# FPGA.net
KiCad netlist of a schematic drawn in Altium Designer
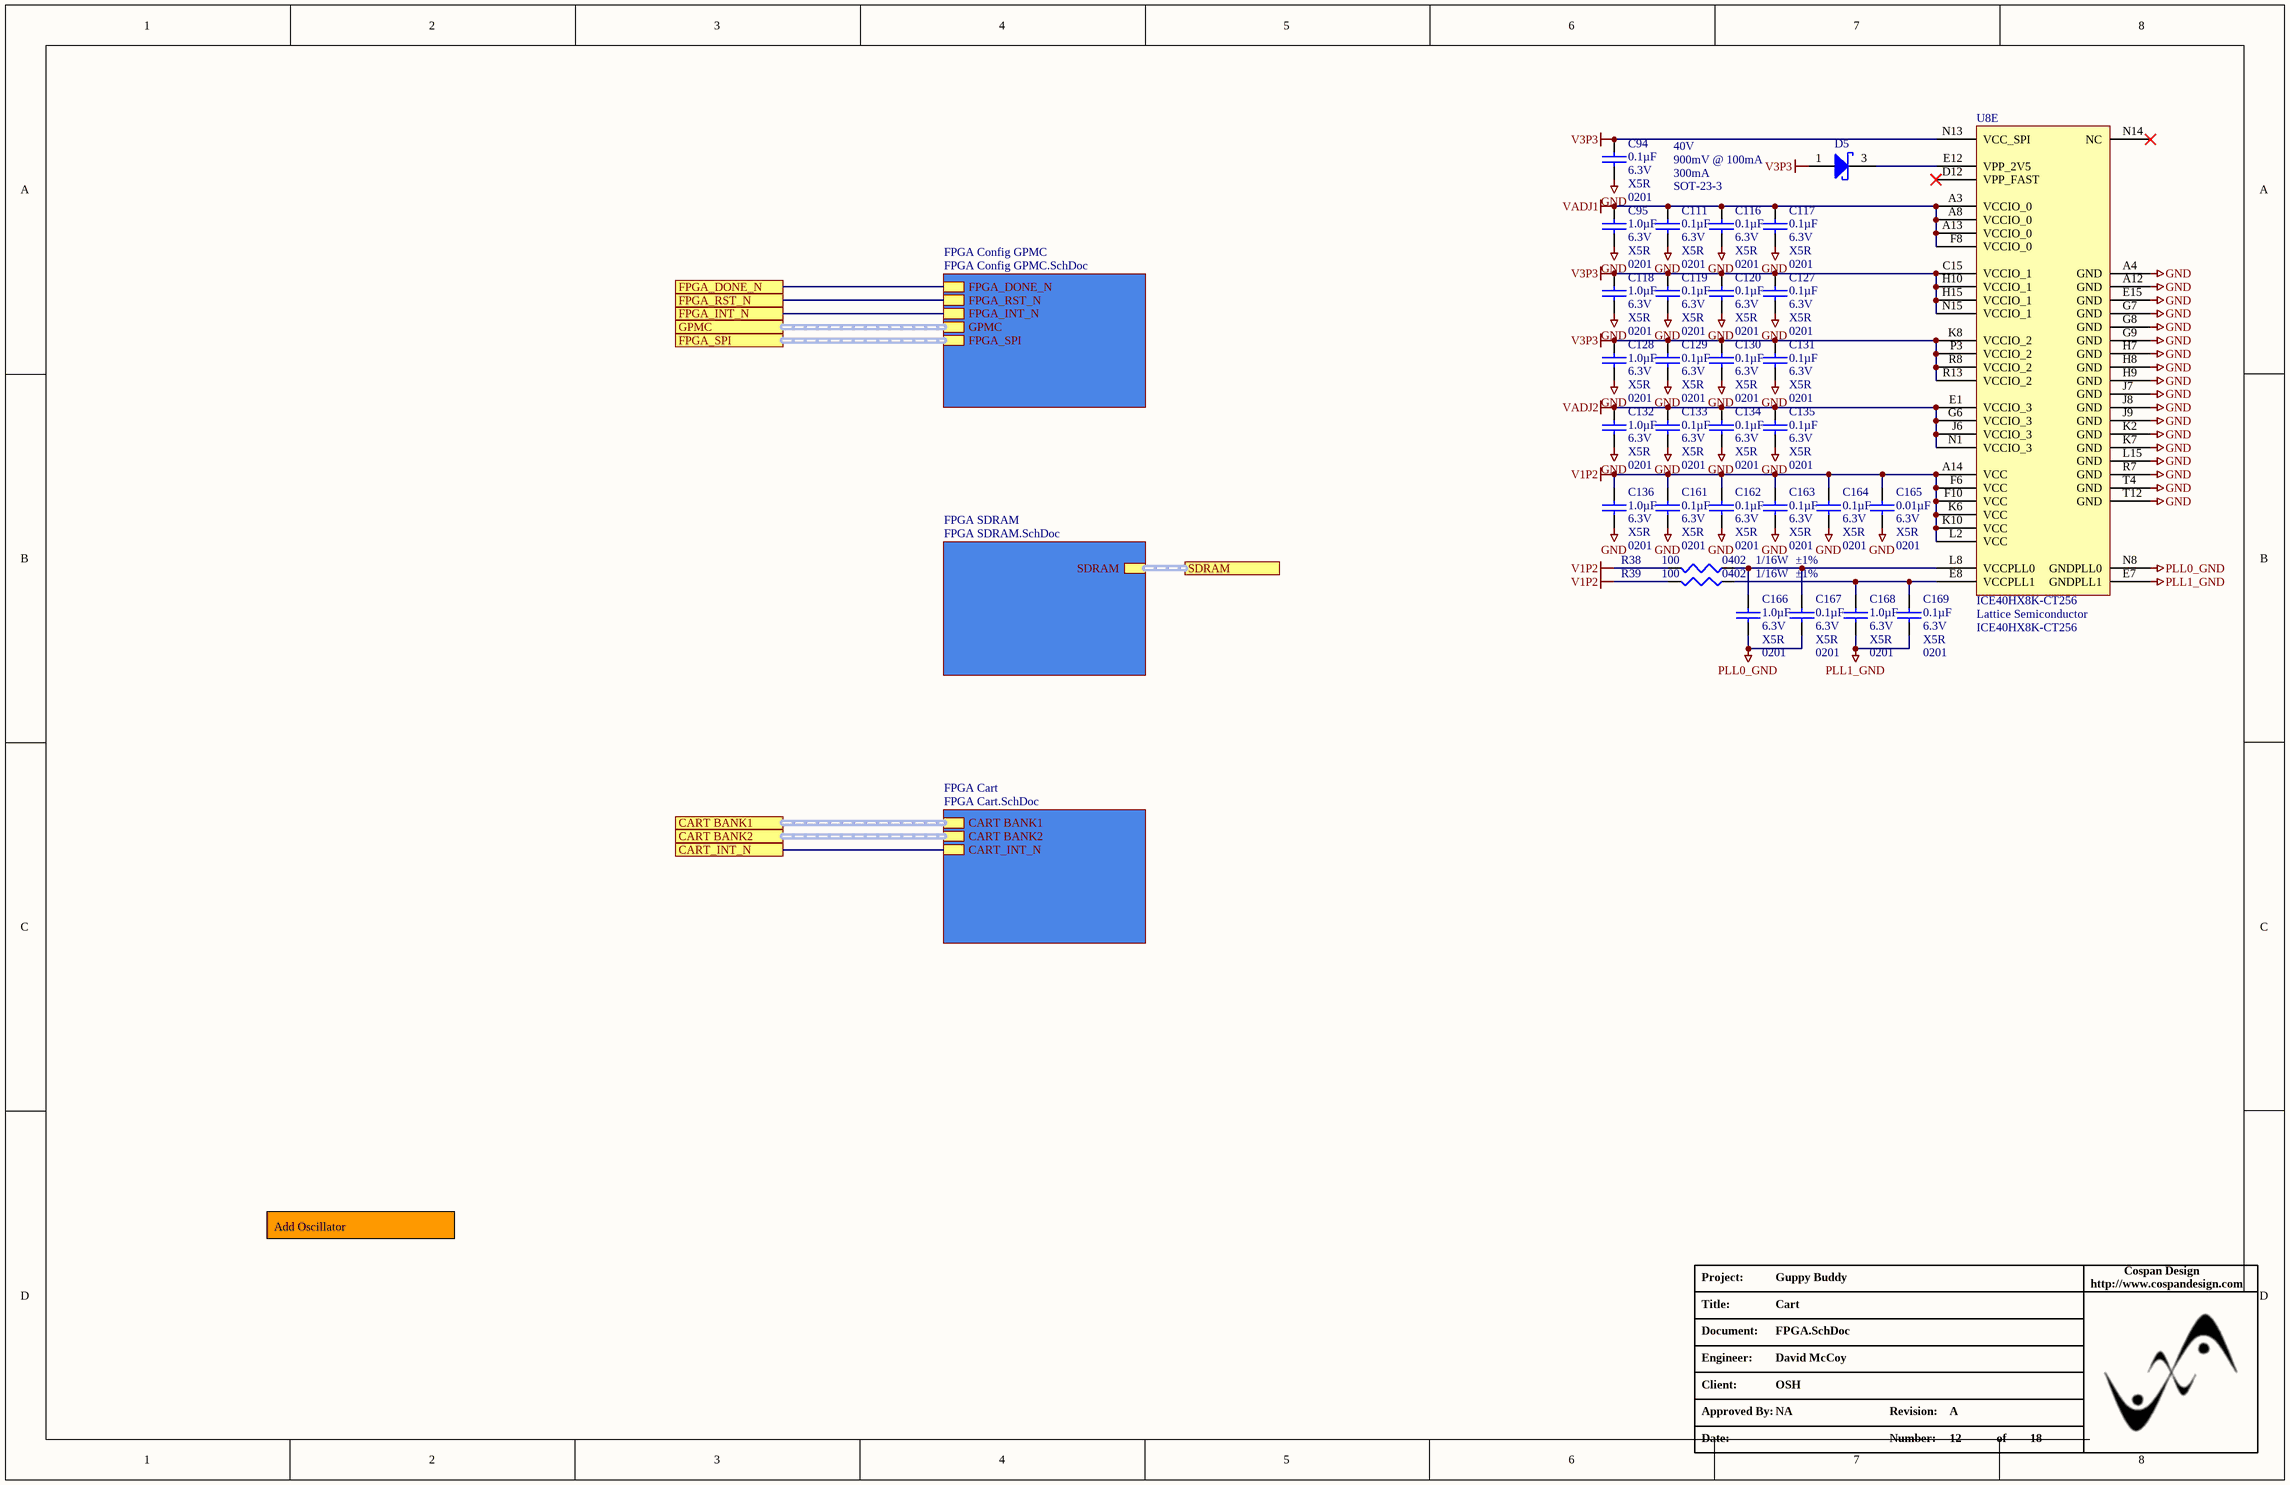
[diagram p0: FPGA.SchDoc]

(export (version "E")
  (design (tool "Eeschema 10.0.6"))
  (components
    (comp (ref "C94")
      (value "0.1UF")
      (footprint "CAPC0201")
      (description "CAP CER 0.1UF 6.3V 10% X5R 0201")
      (fields
        (field (name "MANUFACTURER") "Murata Electronics North America")
        (field (name "MANUFACTURER PART NUMBER") "GRM033R60J104KE19D")
        (field (name "CAPACITANCE") "0.1µF")
        (field (name "VOLTAGE - RATED") "6.3V")
        (field (name "TEMPERATURE COEFFICIENT") "X5R")
        (field (name "PACKAGE / CASE") "0201")
      )
      (libsource (lib "Main Library") (part "C_0201_0.1UF"))
    )
    (comp (ref "C95")
      (value "1.0UF")
      (footprint "CAPC0201")
      (description "CAP CER 1UF 6.3V 20% X5R 0201")
      (fields
        (field (name "MANUFACTURER") "AVX")
        (field (name "MANUFACTURER PART NUMBER") "02016D105KAT2A")
        (field (name "CAPACITANCE") "1.0µF")
        (field (name "VOLTAGE - RATED") "6.3V")
        (field (name "TEMPERATURE COEFFICIENT") "X5R")
        (field (name "PACKAGE / CASE") "0201")
      )
      (libsource (lib "Main Library") (part "C_0201_1.0UF"))
    )
    (comp (ref "C111")
      (value "0.1UF")
      (footprint "CAPC0201")
      (description "CAP CER 0.1UF 6.3V 10% X5R 0201")
      (fields
        (field (name "MANUFACTURER") "Murata Electronics North America")
        (field (name "MANUFACTURER PART NUMBER") "GRM033R60J104KE19D")
        (field (name "CAPACITANCE") "0.1µF")
        (field (name "VOLTAGE - RATED") "6.3V")
        (field (name "TEMPERATURE COEFFICIENT") "X5R")
        (field (name "PACKAGE / CASE") "0201")
      )
      (libsource (lib "Main Library") (part "C_0201_0.1UF"))
    )
    (comp (ref "C116")
      (value "0.1UF")
      (footprint "CAPC0201")
      (description "CAP CER 0.1UF 6.3V 10% X5R 0201")
      (fields
        (field (name "MANUFACTURER") "Murata Electronics North America")
        (field (name "MANUFACTURER PART NUMBER") "GRM033R60J104KE19D")
        (field (name "CAPACITANCE") "0.1µF")
        (field (name "VOLTAGE - RATED") "6.3V")
        (field (name "TEMPERATURE COEFFICIENT") "X5R")
        (field (name "PACKAGE / CASE") "0201")
      )
      (libsource (lib "Main Library") (part "C_0201_0.1UF"))
    )
    (comp (ref "C117")
      (value "0.1UF")
      (footprint "CAPC0201")
      (description "CAP CER 0.1UF 6.3V 10% X5R 0201")
      (fields
        (field (name "MANUFACTURER") "Murata Electronics North America")
        (field (name "MANUFACTURER PART NUMBER") "GRM033R60J104KE19D")
        (field (name "CAPACITANCE") "0.1µF")
        (field (name "VOLTAGE - RATED") "6.3V")
        (field (name "TEMPERATURE COEFFICIENT") "X5R")
        (field (name "PACKAGE / CASE") "0201")
      )
      (libsource (lib "Main Library") (part "C_0201_0.1UF"))
    )
    (comp (ref "C118")
      (value "1.0UF")
      (footprint "CAPC0201")
      (description "CAP CER 1UF 6.3V 20% X5R 0201")
      (fields
        (field (name "MANUFACTURER") "AVX")
        (field (name "MANUFACTURER PART NUMBER") "02016D105KAT2A")
        (field (name "CAPACITANCE") "1.0µF")
        (field (name "VOLTAGE - RATED") "6.3V")
        (field (name "TEMPERATURE COEFFICIENT") "X5R")
        (field (name "PACKAGE / CASE") "0201")
      )
      (libsource (lib "Main Library") (part "C_0201_1.0UF"))
    )
    (comp (ref "C119")
      (value "0.1UF")
      (footprint "CAPC0201")
      (description "CAP CER 0.1UF 6.3V 10% X5R 0201")
      (fields
        (field (name "MANUFACTURER") "Murata Electronics North America")
        (field (name "MANUFACTURER PART NUMBER") "GRM033R60J104KE19D")
        (field (name "CAPACITANCE") "0.1µF")
        (field (name "VOLTAGE - RATED") "6.3V")
        (field (name "TEMPERATURE COEFFICIENT") "X5R")
        (field (name "PACKAGE / CASE") "0201")
      )
      (libsource (lib "Main Library") (part "C_0201_0.1UF"))
    )
    (comp (ref "C120")
      (value "0.1UF")
      (footprint "CAPC0201")
      (description "CAP CER 0.1UF 6.3V 10% X5R 0201")
      (fields
        (field (name "MANUFACTURER") "Murata Electronics North America")
        (field (name "MANUFACTURER PART NUMBER") "GRM033R60J104KE19D")
        (field (name "CAPACITANCE") "0.1µF")
        (field (name "VOLTAGE - RATED") "6.3V")
        (field (name "TEMPERATURE COEFFICIENT") "X5R")
        (field (name "PACKAGE / CASE") "0201")
      )
      (libsource (lib "Main Library") (part "C_0201_0.1UF"))
    )
    (comp (ref "C127")
      (value "0.1UF")
      (footprint "CAPC0201")
      (description "CAP CER 0.1UF 6.3V 10% X5R 0201")
      (fields
        (field (name "MANUFACTURER") "Murata Electronics North America")
        (field (name "MANUFACTURER PART NUMBER") "GRM033R60J104KE19D")
        (field (name "CAPACITANCE") "0.1µF")
        (field (name "VOLTAGE - RATED") "6.3V")
        (field (name "TEMPERATURE COEFFICIENT") "X5R")
        (field (name "PACKAGE / CASE") "0201")
      )
      (libsource (lib "Main Library") (part "C_0201_0.1UF"))
    )
    (comp (ref "C128")
      (value "1.0UF")
      (footprint "CAPC0201")
      (description "CAP CER 1UF 6.3V 20% X5R 0201")
      (fields
        (field (name "MANUFACTURER") "AVX")
        (field (name "MANUFACTURER PART NUMBER") "02016D105KAT2A")
        (field (name "CAPACITANCE") "1.0µF")
        (field (name "VOLTAGE - RATED") "6.3V")
        (field (name "TEMPERATURE COEFFICIENT") "X5R")
        (field (name "PACKAGE / CASE") "0201")
      )
      (libsource (lib "Main Library") (part "C_0201_1.0UF"))
    )
    (comp (ref "C129")
      (value "0.1UF")
      (footprint "CAPC0201")
      (description "CAP CER 0.1UF 6.3V 10% X5R 0201")
      (fields
        (field (name "MANUFACTURER") "Murata Electronics North America")
        (field (name "MANUFACTURER PART NUMBER") "GRM033R60J104KE19D")
        (field (name "CAPACITANCE") "0.1µF")
        (field (name "VOLTAGE - RATED") "6.3V")
        (field (name "TEMPERATURE COEFFICIENT") "X5R")
        (field (name "PACKAGE / CASE") "0201")
      )
      (libsource (lib "Main Library") (part "C_0201_0.1UF"))
    )
    (comp (ref "C130")
      (value "0.1UF")
      (footprint "CAPC0201")
      (description "CAP CER 0.1UF 6.3V 10% X5R 0201")
      (fields
        (field (name "MANUFACTURER") "Murata Electronics North America")
        (field (name "MANUFACTURER PART NUMBER") "GRM033R60J104KE19D")
        (field (name "CAPACITANCE") "0.1µF")
        (field (name "VOLTAGE - RATED") "6.3V")
        (field (name "TEMPERATURE COEFFICIENT") "X5R")
        (field (name "PACKAGE / CASE") "0201")
      )
      (libsource (lib "Main Library") (part "C_0201_0.1UF"))
    )
    (comp (ref "C131")
      (value "0.1UF")
      (footprint "CAPC0201")
      (description "CAP CER 0.1UF 6.3V 10% X5R 0201")
      (fields
        (field (name "MANUFACTURER") "Murata Electronics North America")
        (field (name "MANUFACTURER PART NUMBER") "GRM033R60J104KE19D")
        (field (name "CAPACITANCE") "0.1µF")
        (field (name "VOLTAGE - RATED") "6.3V")
        (field (name "TEMPERATURE COEFFICIENT") "X5R")
        (field (name "PACKAGE / CASE") "0201")
      )
      (libsource (lib "Main Library") (part "C_0201_0.1UF"))
    )
    (comp (ref "C132")
      (value "1.0UF")
      (footprint "CAPC0201")
      (description "CAP CER 1UF 6.3V 20% X5R 0201")
      (fields
        (field (name "MANUFACTURER") "AVX")
        (field (name "MANUFACTURER PART NUMBER") "02016D105KAT2A")
        (field (name "CAPACITANCE") "1.0µF")
        (field (name "VOLTAGE - RATED") "6.3V")
        (field (name "TEMPERATURE COEFFICIENT") "X5R")
        (field (name "PACKAGE / CASE") "0201")
      )
      (libsource (lib "Main Library") (part "C_0201_1.0UF"))
    )
    (comp (ref "C133")
      (value "0.1UF")
      (footprint "CAPC0201")
      (description "CAP CER 0.1UF 6.3V 10% X5R 0201")
      (fields
        (field (name "MANUFACTURER") "Murata Electronics North America")
        (field (name "MANUFACTURER PART NUMBER") "GRM033R60J104KE19D")
        (field (name "CAPACITANCE") "0.1µF")
        (field (name "VOLTAGE - RATED") "6.3V")
        (field (name "TEMPERATURE COEFFICIENT") "X5R")
        (field (name "PACKAGE / CASE") "0201")
      )
      (libsource (lib "Main Library") (part "C_0201_0.1UF"))
    )
    (comp (ref "C134")
      (value "0.1UF")
      (footprint "CAPC0201")
      (description "CAP CER 0.1UF 6.3V 10% X5R 0201")
      (fields
        (field (name "MANUFACTURER") "Murata Electronics North America")
        (field (name "MANUFACTURER PART NUMBER") "GRM033R60J104KE19D")
        (field (name "CAPACITANCE") "0.1µF")
        (field (name "VOLTAGE - RATED") "6.3V")
        (field (name "TEMPERATURE COEFFICIENT") "X5R")
        (field (name "PACKAGE / CASE") "0201")
      )
      (libsource (lib "Main Library") (part "C_0201_0.1UF"))
    )
    (comp (ref "C135")
      (value "0.1UF")
      (footprint "CAPC0201")
      (description "CAP CER 0.1UF 6.3V 10% X5R 0201")
      (fields
        (field (name "MANUFACTURER") "Murata Electronics North America")
        (field (name "MANUFACTURER PART NUMBER") "GRM033R60J104KE19D")
        (field (name "CAPACITANCE") "0.1µF")
        (field (name "VOLTAGE - RATED") "6.3V")
        (field (name "TEMPERATURE COEFFICIENT") "X5R")
        (field (name "PACKAGE / CASE") "0201")
      )
      (libsource (lib "Main Library") (part "C_0201_0.1UF"))
    )
    (comp (ref "C136")
      (value "1.0UF")
      (footprint "CAPC0201")
      (description "CAP CER 1UF 6.3V 20% X5R 0201")
      (fields
        (field (name "MANUFACTURER") "AVX")
        (field (name "MANUFACTURER PART NUMBER") "02016D105KAT2A")
        (field (name "CAPACITANCE") "1.0µF")
        (field (name "VOLTAGE - RATED") "6.3V")
        (field (name "TEMPERATURE COEFFICIENT") "X5R")
        (field (name "PACKAGE / CASE") "0201")
      )
      (libsource (lib "Main Library") (part "C_0201_1.0UF"))
    )
    (comp (ref "C161")
      (value "0.1UF")
      (footprint "CAPC0201")
      (description "CAP CER 0.1UF 6.3V 10% X5R 0201")
      (fields
        (field (name "MANUFACTURER") "Murata Electronics North America")
        (field (name "MANUFACTURER PART NUMBER") "GRM033R60J104KE19D")
        (field (name "CAPACITANCE") "0.1µF")
        (field (name "VOLTAGE - RATED") "6.3V")
        (field (name "TEMPERATURE COEFFICIENT") "X5R")
        (field (name "PACKAGE / CASE") "0201")
      )
      (libsource (lib "Main Library") (part "C_0201_0.1UF"))
    )
    (comp (ref "C162")
      (value "0.1UF")
      (footprint "CAPC0201")
      (description "CAP CER 0.1UF 6.3V 10% X5R 0201")
      (fields
        (field (name "MANUFACTURER") "Murata Electronics North America")
        (field (name "MANUFACTURER PART NUMBER") "GRM033R60J104KE19D")
        (field (name "CAPACITANCE") "0.1µF")
        (field (name "VOLTAGE - RATED") "6.3V")
        (field (name "TEMPERATURE COEFFICIENT") "X5R")
        (field (name "PACKAGE / CASE") "0201")
      )
      (libsource (lib "Main Library") (part "C_0201_0.1UF"))
    )
    (comp (ref "C163")
      (value "0.1UF")
      (footprint "CAPC0201")
      (description "CAP CER 0.1UF 6.3V 10% X5R 0201")
      (fields
        (field (name "MANUFACTURER") "Murata Electronics North America")
        (field (name "MANUFACTURER PART NUMBER") "GRM033R60J104KE19D")
        (field (name "CAPACITANCE") "0.1µF")
        (field (name "VOLTAGE - RATED") "6.3V")
        (field (name "TEMPERATURE COEFFICIENT") "X5R")
        (field (name "PACKAGE / CASE") "0201")
      )
      (libsource (lib "Main Library") (part "C_0201_0.1UF"))
    )
    (comp (ref "C164")
      (value "0.1UF")
      (footprint "CAPC0201")
      (description "CAP CER 0.1UF 6.3V 10% X5R 0201")
      (fields
        (field (name "MANUFACTURER") "Murata Electronics North America")
        (field (name "MANUFACTURER PART NUMBER") "GRM033R60J104KE19D")
        (field (name "CAPACITANCE") "0.1µF")
        (field (name "VOLTAGE - RATED") "6.3V")
        (field (name "TEMPERATURE COEFFICIENT") "X5R")
        (field (name "PACKAGE / CASE") "0201")
      )
      (libsource (lib "Main Library") (part "C_0201_0.1UF"))
    )
    (comp (ref "C165")
      (value "0.01UF")
      (footprint "CAPC0201")
      (description "CAP CER 10000PF 6.3V X5R 0201")
      (fields
        (field (name "MANUFACTURER") "TDK Corporation")
        (field (name "MANUFACTURER PART NUMBER") "C0603X5R0J103M")
        (field (name "CAPACITANCE") "0.01µF")
        (field (name "VOLTAGE - RATED") "6.3V")
        (field (name "TEMPERATURE COEFFICIENT") "X5R")
        (field (name "PACKAGE / CASE") "0201")
      )
      (libsource (lib "Main Library") (part "C_0201_0.01UF"))
    )
    (comp (ref "C166")
      (value "1.0UF")
      (footprint "CAPC0201")
      (description "CAP CER 1UF 6.3V 20% X5R 0201")
      (fields
        (field (name "MANUFACTURER") "AVX")
        (field (name "MANUFACTURER PART NUMBER") "02016D105KAT2A")
        (field (name "CAPACITANCE") "1.0µF")
        (field (name "VOLTAGE - RATED") "6.3V")
        (field (name "TEMPERATURE COEFFICIENT") "X5R")
        (field (name "PACKAGE / CASE") "0201")
      )
      (libsource (lib "Main Library") (part "C_0201_1.0UF"))
    )
    (comp (ref "C167")
      (value "0.1UF")
      (footprint "CAPC0201")
      (description "CAP CER 0.1UF 6.3V 10% X5R 0201")
      (fields
        (field (name "MANUFACTURER") "Murata Electronics North America")
        (field (name "MANUFACTURER PART NUMBER") "GRM033R60J104KE19D")
        (field (name "CAPACITANCE") "0.1µF")
        (field (name "VOLTAGE - RATED") "6.3V")
        (field (name "TEMPERATURE COEFFICIENT") "X5R")
        (field (name "PACKAGE / CASE") "0201")
      )
      (libsource (lib "Main Library") (part "C_0201_0.1UF"))
    )
    (comp (ref "C168")
      (value "1.0UF")
      (footprint "CAPC0201")
      (description "CAP CER 1UF 6.3V 20% X5R 0201")
      (fields
        (field (name "MANUFACTURER") "AVX")
        (field (name "MANUFACTURER PART NUMBER") "02016D105KAT2A")
        (field (name "CAPACITANCE") "1.0µF")
        (field (name "VOLTAGE - RATED") "6.3V")
        (field (name "TEMPERATURE COEFFICIENT") "X5R")
        (field (name "PACKAGE / CASE") "0201")
      )
      (libsource (lib "Main Library") (part "C_0201_1.0UF"))
    )
    (comp (ref "C169")
      (value "0.1UF")
      (footprint "CAPC0201")
      (description "CAP CER 0.1UF 6.3V 10% X5R 0201")
      (fields
        (field (name "MANUFACTURER") "Murata Electronics North America")
        (field (name "MANUFACTURER PART NUMBER") "GRM033R60J104KE19D")
        (field (name "CAPACITANCE") "0.1µF")
        (field (name "VOLTAGE - RATED") "6.3V")
        (field (name "TEMPERATURE COEFFICIENT") "X5R")
        (field (name "PACKAGE / CASE") "0201")
      )
      (libsource (lib "Main Library") (part "C_0201_0.1UF"))
    )
    (comp (ref "D5")
      (value "BAT54")
      (footprint "SOT23")
      (description "DIODE SCHOTTKY 40V 300MA SOT-23")
      (fields
        (field (name "VOLTAGE - DC REVERSE (VR) (MAX)") "40V")
        (field (name "VOLTAGE - FORWARD (VF) (MAX) @ IF") "900mV @ 100mA")
        (field (name "CURRENT - AVERAGE RECTIFIED (IO)") "300mA")
        (field (name "PACKAGE / CASE") "SOT-23-3")
      )
      (libsource (lib "Main Library") (part "D_SCHOTT_BAT54WFILM"))
    )
    (comp (ref "R38")
      (value "R_0402_100.0")
      (footprint "R_0402")
      (description "RES 100 OHM 1/16W 1% 0402 SMD")
      (fields
        (field (name "MANUFACTURER") "Yageo")
        (field (name "MANUFACTURER PART NUMBER") "RC0402FR-07100RL")
        (field (name "CASE") "0402")
        (field (name "RESISTANCE IN OHMS") "100")
        (field (name "POWER (WATTS)") "1/16W")
        (field (name "TOLERANCE") "±1%")
      )
      (libsource (lib "Main Library") (part "R_0402_100.0"))
    )
    (comp (ref "R39")
      (value "R_0402_100.0")
      (footprint "R_0402")
      (description "RES 100 OHM 1/16W 1% 0402 SMD")
      (fields
        (field (name "MANUFACTURER") "Yageo")
        (field (name "MANUFACTURER PART NUMBER") "RC0402FR-07100RL")
        (field (name "CASE") "0402")
        (field (name "RESISTANCE IN OHMS") "100")
        (field (name "POWER (WATTS)") "1/16W")
        (field (name "TOLERANCE") "±1%")
      )
      (libsource (lib "Main Library") (part "R_0402_100.0"))
    )
    (comp (ref "U8")
      (value "ICE40HX8K-CT256")
      (footprint "LATC-caBGA-256")
      (fields
        (field (name "MANUFACTURER") "Lattice Semiconductor")
        (field (name "MANUFACTURER 1") "Lattice Semiconductor")
        (field (name "MANUFACTURER PART NUMBER 1") "ICE40HX8K-CT256")
      )
      (libsource (lib "Cospan Design") (part "U_ICE40HX8K-CT256"))
    )
  )
  (nets
    (net (code "16") (name "GND") (class "Default")
      (node (ref "C111") (pin "1") (pinfunction "1_1") (pintype "passive"))
      (node (ref "C116") (pin "1") (pinfunction "1_1") (pintype "passive"))
      (node (ref "C117") (pin "1") (pinfunction "1_1") (pintype "passive"))
      (node (ref "C118") (pin "1") (pinfunction "1_1") (pintype "passive"))
      (node (ref "C119") (pin "1") (pinfunction "1_1") (pintype "passive"))
      (node (ref "C120") (pin "1") (pinfunction "1_1") (pintype "passive"))
      (node (ref "C127") (pin "1") (pinfunction "1_1") (pintype "passive"))
      (node (ref "C128") (pin "1") (pinfunction "1_1") (pintype "passive"))
      (node (ref "C129") (pin "1") (pinfunction "1_1") (pintype "passive"))
      (node (ref "C130") (pin "1") (pinfunction "1_1") (pintype "passive"))
      (node (ref "C131") (pin "1") (pinfunction "1_1") (pintype "passive"))
      (node (ref "C132") (pin "1") (pinfunction "1_1") (pintype "passive"))
      (node (ref "C133") (pin "1") (pinfunction "1_1") (pintype "passive"))
      (node (ref "C134") (pin "1") (pinfunction "1_1") (pintype "passive"))
      (node (ref "C135") (pin "1") (pinfunction "1_1") (pintype "passive"))
      (node (ref "C136") (pin "1") (pinfunction "1_1") (pintype "passive"))
      (node (ref "C161") (pin "1") (pinfunction "1_1") (pintype "passive"))
      (node (ref "C162") (pin "1") (pinfunction "1_1") (pintype "passive"))
      (node (ref "C163") (pin "1") (pinfunction "1_1") (pintype "passive"))
      (node (ref "C164") (pin "1") (pinfunction "1_1") (pintype "passive"))
      (node (ref "C165") (pin "1") (pinfunction "1_1") (pintype "passive"))
      (node (ref "C94") (pin "1") (pinfunction "1_1") (pintype "passive"))
      (node (ref "C95") (pin "1") (pinfunction "1_1") (pintype "passive"))
      (node (ref "U8") (pin "A12") (pinfunction "GND_A12") (pintype "power_in"))
      (node (ref "U8") (pin "A4") (pinfunction "GND_A4") (pintype "power_in"))
      (node (ref "U8") (pin "E15") (pinfunction "GND_E15") (pintype "power_in"))
      (node (ref "U8") (pin "G7") (pinfunction "GND_G7") (pintype "power_in"))
      (node (ref "U8") (pin "G8") (pinfunction "GND_G8") (pintype "power_in"))
      (node (ref "U8") (pin "G9") (pinfunction "GND_G9") (pintype "power_in"))
      (node (ref "U8") (pin "H7") (pinfunction "GND_H7") (pintype "power_in"))
      (node (ref "U8") (pin "H8") (pinfunction "GND_H8") (pintype "power_in"))
      (node (ref "U8") (pin "H9") (pinfunction "GND_H9") (pintype "power_in"))
      (node (ref "U8") (pin "J7") (pinfunction "GND_J7") (pintype "power_in"))
      (node (ref "U8") (pin "J8") (pinfunction "GND_J8") (pintype "power_in"))
      (node (ref "U8") (pin "J9") (pinfunction "GND_J9") (pintype "power_in"))
      (node (ref "U8") (pin "K2") (pinfunction "GND_K2") (pintype "power_in"))
      (node (ref "U8") (pin "K7") (pinfunction "GND_K7") (pintype "power_in"))
      (node (ref "U8") (pin "L15") (pinfunction "GND_L15") (pintype "power_in"))
      (node (ref "U8") (pin "R7") (pinfunction "GND_R7") (pintype "power_in"))
      (node (ref "U8") (pin "T12") (pinfunction "GND_T12") (pintype "power_in"))
      (node (ref "U8") (pin "T4") (pinfunction "GND_T4") (pintype "power_in"))
    )
    (net (code "17") (name "Net-(D5-K)") (class "Default")
      (node (ref "D5") (pin "3") (pinfunction "K_3") (pintype "passive"))
      (node (ref "U8") (pin "E12") (pinfunction "VPP_2V5_E12") (pintype "power_in"))
    )
    (net (code "18") (name "Net-(U8E-VCCPLL0)") (class "Default")
      (node (ref "C166") (pin "2") (pinfunction "2_2") (pintype "passive"))
      (node (ref "C167") (pin "2") (pinfunction "2_2") (pintype "passive"))
      (node (ref "R38") (pin "2") (pinfunction "2_2") (pintype "passive"))
      (node (ref "U8") (pin "L8") (pinfunction "VCCPLL0_L8") (pintype "power_in"))
    )
    (net (code "19") (name "Net-(U8E-VCCPLL1)") (class "Default")
      (node (ref "C168") (pin "2") (pinfunction "2_2") (pintype "passive"))
      (node (ref "C169") (pin "2") (pinfunction "2_2") (pintype "passive"))
      (node (ref "R39") (pin "2") (pinfunction "2_2") (pintype "passive"))
      (node (ref "U8") (pin "E8") (pinfunction "VCCPLL1_E8") (pintype "power_in"))
    )
    (net (code "20") (name "PLL0_GND") (class "Default")
      (node (ref "C166") (pin "1") (pinfunction "1_1") (pintype "passive"))
      (node (ref "C167") (pin "1") (pinfunction "1_1") (pintype "passive"))
      (node (ref "U8") (pin "N8") (pinfunction "GNDPLL0_N8") (pintype "power_in"))
    )
    (net (code "21") (name "PLL1_GND") (class "Default")
      (node (ref "C168") (pin "1") (pinfunction "1_1") (pintype "passive"))
      (node (ref "C169") (pin "1") (pinfunction "1_1") (pintype "passive"))
      (node (ref "U8") (pin "E7") (pinfunction "GNDPLL1_E7") (pintype "power_in"))
    )
    (net (code "22") (name "V1P2") (class "Default")
      (node (ref "C136") (pin "2") (pinfunction "2_2") (pintype "passive"))
      (node (ref "C161") (pin "2") (pinfunction "2_2") (pintype "passive"))
      (node (ref "C162") (pin "2") (pinfunction "2_2") (pintype "passive"))
      (node (ref "C163") (pin "2") (pinfunction "2_2") (pintype "passive"))
      (node (ref "C164") (pin "2") (pinfunction "2_2") (pintype "passive"))
      (node (ref "C165") (pin "2") (pinfunction "2_2") (pintype "passive"))
      (node (ref "R38") (pin "1") (pinfunction "1_1") (pintype "passive"))
      (node (ref "R39") (pin "1") (pinfunction "1_1") (pintype "passive"))
      (node (ref "U8") (pin "A14") (pinfunction "VCC_A14") (pintype "power_in"))
      (node (ref "U8") (pin "F10") (pinfunction "VCC_F10") (pintype "power_in"))
      (node (ref "U8") (pin "F6") (pinfunction "VCC_F6") (pintype "power_in"))
      (node (ref "U8") (pin "K10") (pinfunction "VCC_K10") (pintype "power_in"))
      (node (ref "U8") (pin "K6") (pinfunction "VCC_K6") (pintype "power_in"))
      (node (ref "U8") (pin "L2") (pinfunction "VCC_L2") (pintype "power_in"))
    )
    (net (code "23") (name "V3P3") (class "Default")
      (node (ref "C118") (pin "2") (pinfunction "2_2") (pintype "passive"))
      (node (ref "C119") (pin "2") (pinfunction "2_2") (pintype "passive"))
      (node (ref "C120") (pin "2") (pinfunction "2_2") (pintype "passive"))
      (node (ref "C127") (pin "2") (pinfunction "2_2") (pintype "passive"))
      (node (ref "C128") (pin "2") (pinfunction "2_2") (pintype "passive"))
      (node (ref "C129") (pin "2") (pinfunction "2_2") (pintype "passive"))
      (node (ref "C130") (pin "2") (pinfunction "2_2") (pintype "passive"))
      (node (ref "C131") (pin "2") (pinfunction "2_2") (pintype "passive"))
      (node (ref "C94") (pin "2") (pinfunction "2_2") (pintype "passive"))
      (node (ref "D5") (pin "1") (pinfunction "A_1") (pintype "passive"))
      (node (ref "U8") (pin "C15") (pinfunction "VCCIO_1_C15") (pintype "power_in"))
      (node (ref "U8") (pin "H10") (pinfunction "VCCIO_1_H10") (pintype "power_in"))
      (node (ref "U8") (pin "H15") (pinfunction "VCCIO_1_H15") (pintype "power_in"))
      (node (ref "U8") (pin "K8") (pinfunction "VCCIO_2_K8") (pintype "power_in"))
      (node (ref "U8") (pin "N13") (pinfunction "VCC_SPI_N13") (pintype "power_in"))
      (node (ref "U8") (pin "N15") (pinfunction "VCCIO_1_N15") (pintype "power_in"))
      (node (ref "U8") (pin "P3") (pinfunction "VCCIO_2_P3") (pintype "power_in"))
      (node (ref "U8") (pin "R13") (pinfunction "VCCIO_2_R13") (pintype "power_in"))
      (node (ref "U8") (pin "R8") (pinfunction "VCCIO_2_R8") (pintype "power_in"))
    )
    (net (code "24") (name "VADJ1") (class "Default")
      (node (ref "C111") (pin "2") (pinfunction "2_2") (pintype "passive"))
      (node (ref "C116") (pin "2") (pinfunction "2_2") (pintype "passive"))
      (node (ref "C117") (pin "2") (pinfunction "2_2") (pintype "passive"))
      (node (ref "C95") (pin "2") (pinfunction "2_2") (pintype "passive"))
      (node (ref "U8") (pin "A13") (pinfunction "VCCIO_0_A13") (pintype "power_in"))
      (node (ref "U8") (pin "A3") (pinfunction "VCCIO_0_A3") (pintype "power_in"))
      (node (ref "U8") (pin "A8") (pinfunction "VCCIO_0_A8") (pintype "power_in"))
      (node (ref "U8") (pin "F8") (pinfunction "VCCIO_0_F8") (pintype "power_in"))
    )
    (net (code "25") (name "VADJ2") (class "Default")
      (node (ref "C132") (pin "2") (pinfunction "2_2") (pintype "passive"))
      (node (ref "C133") (pin "2") (pinfunction "2_2") (pintype "passive"))
      (node (ref "C134") (pin "2") (pinfunction "2_2") (pintype "passive"))
      (node (ref "C135") (pin "2") (pinfunction "2_2") (pintype "passive"))
      (node (ref "U8") (pin "E1") (pinfunction "VCCIO_3_E1") (pintype "power_in"))
      (node (ref "U8") (pin "G6") (pinfunction "VCCIO_3_G6") (pintype "power_in"))
      (node (ref "U8") (pin "J6") (pinfunction "VCCIO_3_J6") (pintype "power_in"))
      (node (ref "U8") (pin "N1") (pinfunction "VCCIO_3_N1") (pintype "power_in"))
    )
    (net (code "26") (name "unconnected-(U8E-NC-PadN14)") (class "Default")
      (node (ref "U8") (pin "N14") (pinfunction "NC_N14") (pintype "passive+no_connect"))
    )
    (net (code "27") (name "unconnected-(U8E-VPP_FAST-PadD12)") (class "Default")
      (node (ref "U8") (pin "D12") (pinfunction "VPP_FAST_D12") (pintype "power_in+no_connect"))
    )
  )
)
